# batt.net
KiCad netlist of a schematic drawn in Altium Designer
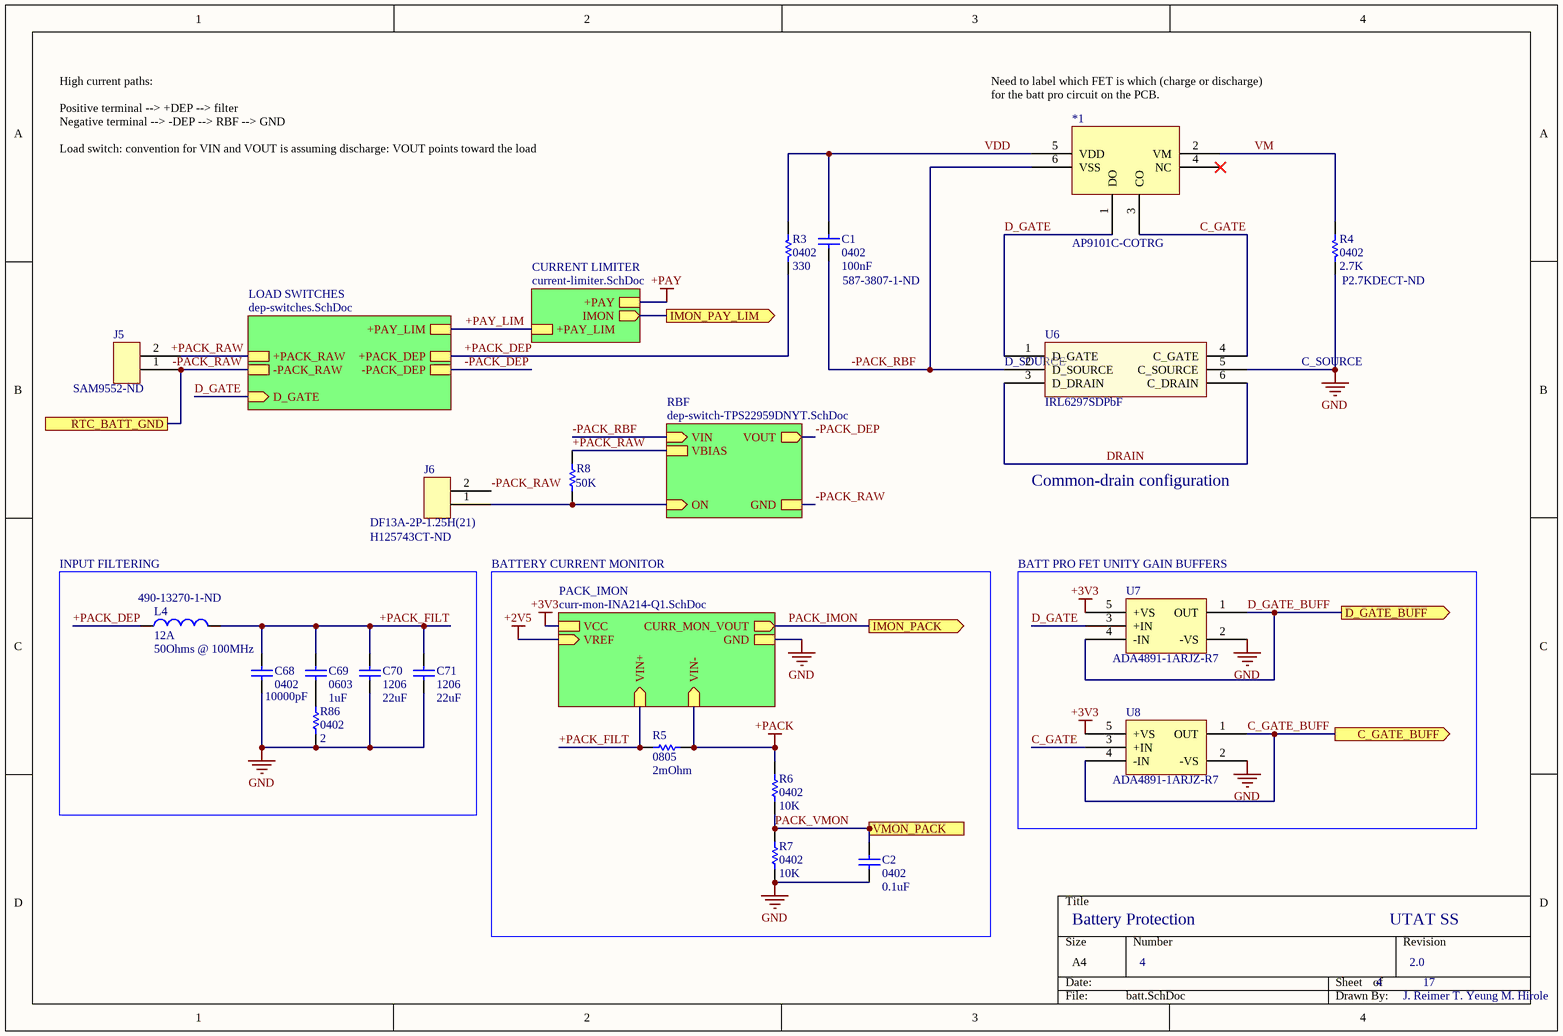
[diagram p0: batt.SchDoc]

(export (version "E")
  (design (tool "Eeschema 10.0.6"))
  (components
    (comp (ref "*1")
      (value "AP9101C-COTRG")
      (footprint "SOT-26")
      (description "Battery Protection IC")
      (libsource (lib "heron-general") (part "AP9101C-COTRG"))
    )
    (comp (ref "C1")
      (value "0402")
      (footprint "CAP0402R")
      (description "0402 capacitor")
      (fields
        (field (name "ALTIUM_VALUE") "100nF")
        (field (name "SUPPLIER PART NUMBER 1") "587-3807-1-ND")
        (field (name "MANUFACTURER") "Taiyo Yuden")
        (field (name "MANUFACTURER PART NUMBER") "EMK105B7104KVHF")
      )
      (libsource (lib "heron-general") (part "CAP0402"))
    )
    (comp (ref "C2")
      (value "0402")
      (footprint "CAP0402R")
      (description "0402 capacitor")
      (fields (field (name "ALTIUM_VALUE") "0.1uF"))
      (libsource (lib "heron-general") (part "CAP0402"))
    )
    (comp (ref "C68")
      (value "0402")
      (footprint "CAP0402R")
      (description "Capacitor")
      (fields (field (name "ALTIUM_VALUE") "10000pF") (field (name "PUBLISHER") "Altium Limited"))
      (libsource (lib "Miscellaneous Devices") (part "Cap"))
    )
    (comp (ref "C69")
      (value "0603")
      (footprint "CAP0603R")
      (description "Capacitor")
      (fields (field (name "ALTIUM_VALUE") "1uF") (field (name "PUBLISHER") "Altium Limited"))
      (libsource (lib "Miscellaneous Devices") (part "Cap"))
    )
    (comp (ref "C70")
      (value "1206")
      (footprint "CAP1206R")
      (description "1206 capacitor")
      (fields (field (name "ALTIUM_VALUE") "22uF"))
      (libsource (lib "heron-general") (part "CAP1206"))
    )
    (comp (ref "C71")
      (value "1206")
      (footprint "CAP1206R")
      (description "1206 capacitor")
      (fields (field (name "ALTIUM_VALUE") "22uF"))
      (libsource (lib "heron-general") (part "CAP1206"))
    )
    (comp (ref "J5")
      (value "IPBT-102-H1-T-S-RA-K")
      (footprint "SAM9552-ND")
      (description "Samtec Connector Through Hole, Right Angle 2 pos 0.165\" (4.20mm) pitch")
      (fields (field (name "SUPPLIER PART NUMBER 1") "SAM9552-ND"))
      (libsource (lib "heron-general") (part "IPBT-102-H1-T-S-RA-K"))
    )
    (comp (ref "J6")
      (value "DF13A-2P-1.25H(21)")
      (footprint "DF13A-2P-1.25H(21)")
      (description "2 pos DF13 right angle surface mount connector")
      (fields (field (name "SUPPLIER PART NUMBER 1") "H125743CT-ND"))
      (libsource (lib "heron-general") (part "DF13A-2P-1.25H(21)"))
    )
    (comp (ref "L4")
      (value "12A")
      (footprint "CAP1206R")
      (description "Inductor 50Ohms @ 100MHz")
      (fields
        (field (name "ALTIUM_VALUE") "50Ohms @ 100MHz")
        (field (name "SUPPLIER PART NUMBER 3") "490-13270-1-ND")
        (field (name "PUBLISHER") "Altium Limited")
      )
      (libsource (lib "Miscellaneous Devices") (part "Inductor"))
    )
    (comp (ref "R3")
      (value "0402")
      (footprint "RES0402R")
      (description "0402 resistor")
      (fields (field (name "ALTIUM_VALUE") "330"))
      (libsource (lib "heron-general") (part "RES0402"))
    )
    (comp (ref "R4")
      (value "0402")
      (footprint "RES0402R")
      (description "0402 resistor")
      (fields
        (field (name "ALTIUM_VALUE") "2.7K")
        (field (name "SUPPLIER PART NUMBER 1") "P2.7KDECT-ND")
        (field (name "MANUFACTURER") "Panasonic")
        (field (name "MANUFACTURER PART NUMBER") "ERA-2AED272X")
      )
      (libsource (lib "heron-general") (part "RES0402"))
    )
    (comp (ref "R5")
      (value "0805")
      (footprint "RES0805R")
      (description "0805 resistor")
      (fields
        (field (name "ALTIUM_VALUE") "2mOhm")
        (field (name "MANUFACTURER") "Panasonic")
        (field (name "MANUFACTURER PART NUMBER") "ERJ-8BWJR010V")
      )
      (libsource (lib "heron-general") (part "RES0805"))
    )
    (comp (ref "R6")
      (value "0402")
      (footprint "RES0402R")
      (description "0402 resistor")
      (fields (field (name "ALTIUM_VALUE") "10K"))
      (libsource (lib "heron-general") (part "RES0402"))
    )
    (comp (ref "R7")
      (value "0402")
      (footprint "RES0402R")
      (description "0402 resistor")
      (fields (field (name "ALTIUM_VALUE") "10K"))
      (libsource (lib "heron-general") (part "RES0402"))
    )
    (comp (ref "R8")
      (value "50K")
      (footprint "RES0402R")
      (description "0402 resistor")
      (fields (field (name "Comment") "0402"))
      (libsource (lib "heron-general") (part "RES0402"))
    )
    (comp (ref "R86")
      (value "0402")
      (footprint "RES0402R")
      (description "Resistor")
      (fields (field (name "ALTIUM_VALUE") "2") (field (name "PUBLISHER") "Altium Limited"))
      (libsource (lib "Miscellaneous Devices") (part "Res1"))
    )
    (comp (ref "U6")
      (value "IRL6297SDPbF")
      (footprint "IRL6297SDPbF")
      (libsource (lib "heron-general") (part "IRL6297SDPbF"))
    )
    (comp (ref "U7")
      (value "ADA4891-1ARJZ-R7")
      (footprint "SOT-23-5")
      (description "Rail-to-rail amplifier 125mA max")
      (fields (field (name "COPYRIGHT") "Copyright (C) 2018 Accelerated Designs. All rights reserved"))
      (libsource (lib "heron-general") (part "ADA4891-1ARJZ-R7"))
    )
    (comp (ref "U8")
      (value "ADA4891-1ARJZ-R7")
      (footprint "SOT-23-5")
      (description "Rail-to-rail amplifier 125mA max")
      (fields (field (name "COPYRIGHT") "Copyright (C) 2018 Accelerated Designs. All rights reserved"))
      (libsource (lib "heron-general") (part "ADA4891-1ARJZ-R7"))
    )
  )
  (nets
    (net (code "2") (name "+3V3") (class "Default")
      (node (ref "U7") (pin "5") (pinfunction "+VS_5") (pintype "passive"))
      (node (ref "U8") (pin "5") (pinfunction "+VS_5") (pintype "passive"))
    )
    (net (code "3") (name "+PACK") (class "Default")
      (node (ref "R5") (pin "2") (pinfunction "2_2") (pintype "passive"))
      (node (ref "R6") (pin "2") (pinfunction "2_2") (pintype "passive"))
    )
    (net (code "5") (name "/+PACK_DEP") (class "Default")
      (node (ref "L4") (pin "1") (pinfunction "1_1") (pintype "passive"))
      (node (ref "R3") (pin "2") (pinfunction "2_2") (pintype "passive"))
    )
    (net (code "6") (name "/+PACK_FILT") (class "Default")
      (node (ref "C68") (pin "2") (pinfunction "2_2") (pintype "passive"))
      (node (ref "C69") (pin "2") (pinfunction "2_2") (pintype "passive"))
      (node (ref "C70") (pin "2") (pinfunction "2_2") (pintype "passive"))
      (node (ref "C71") (pin "2") (pinfunction "2_2") (pintype "passive"))
      (node (ref "L4") (pin "2") (pinfunction "2_2") (pintype "passive"))
      (node (ref "R5") (pin "1") (pinfunction "1_1") (pintype "passive"))
    )
    (net (code "7") (name "/+PACK_RAW") (class "Default")
      (node (ref "J5") (pin "2") (pinfunction "2_2") (pintype "passive"))
      (node (ref "R8") (pin "2") (pinfunction "2_2") (pintype "passive"))
    )
    (net (code "10") (name "/-PACK_RAW") (class "Default")
      (node (ref "J5") (pin "1") (pinfunction "1_1") (pintype "passive"))
      (node (ref "J6") (pin "2") (pintype "passive"))
    )
    (net (code "11") (name "/-PACK_RBF") (class "Default")
      (node (ref "*1") (pin "6") (pinfunction "VSS_6") (pintype "passive"))
      (node (ref "C1") (pin "1") (pinfunction "1_1") (pintype "passive"))
      (node (ref "U6") (pin "2") (pinfunction "D_SOURCE_2") (pintype "passive"))
    )
    (net (code "13") (name "/C_GATE") (class "Default")
      (node (ref "*1") (pin "3") (pinfunction "CO_3") (pintype "passive"))
      (node (ref "U6") (pin "4") (pinfunction "C_GATE_4") (pintype "passive"))
      (node (ref "U8") (pin "3") (pinfunction "+IN_3") (pintype "passive"))
    )
    (net (code "14") (name "/C_GATE_BUFF") (class "Default")
      (node (ref "U8") (pin "1") (pinfunction "OUT_1") (pintype "passive"))
      (node (ref "U8") (pin "4") (pinfunction "-IN_4") (pintype "passive"))
    )
    (net (code "15") (name "/DRAIN") (class "Default")
      (node (ref "U6") (pin "3") (pinfunction "D_DRAIN_3") (pintype "passive"))
      (node (ref "U6") (pin "6") (pinfunction "C_DRAIN_6") (pintype "passive"))
    )
    (net (code "16") (name "/D_GATE") (class "Default")
      (node (ref "*1") (pin "1") (pinfunction "DO_1") (pintype "passive"))
      (node (ref "U6") (pin "1") (pinfunction "D_GATE_1") (pintype "passive"))
      (node (ref "U7") (pin "3") (pinfunction "+IN_3") (pintype "passive"))
    )
    (net (code "17") (name "/D_GATE_BUFF") (class "Default")
      (node (ref "U7") (pin "1") (pinfunction "OUT_1") (pintype "passive"))
      (node (ref "U7") (pin "4") (pinfunction "-IN_4") (pintype "passive"))
    )
    (net (code "19") (name "/ON") (class "Default")
      (node (ref "J6") (pin "1") (pintype "passive"))
      (node (ref "R8") (pin "1") (pinfunction "1_1") (pintype "passive"))
    )
    (net (code "21") (name "/PACK_VMON") (class "Default")
      (node (ref "C2") (pin "2") (pinfunction "2_2") (pintype "passive"))
      (node (ref "R6") (pin "1") (pinfunction "1_1") (pintype "passive"))
      (node (ref "R7") (pin "2") (pinfunction "2_2") (pintype "passive"))
    )
    (net (code "22") (name "/VDD") (class "Default")
      (node (ref "*1") (pin "5") (pinfunction "VDD_5") (pintype "passive"))
      (node (ref "C1") (pin "2") (pinfunction "2_2") (pintype "passive"))
      (node (ref "R3") (pin "1") (pinfunction "1_1") (pintype "passive"))
    )
    (net (code "23") (name "/VM") (class "Default")
      (node (ref "*1") (pin "2") (pinfunction "VM_2") (pintype "passive"))
      (node (ref "R4") (pin "2") (pinfunction "2_2") (pintype "passive"))
    )
    (net (code "24") (name "GND") (class "Default")
      (node (ref "C2") (pin "1") (pinfunction "1_1") (pintype "passive"))
      (node (ref "C68") (pin "1") (pinfunction "1_1") (pintype "passive"))
      (node (ref "C70") (pin "1") (pinfunction "1_1") (pintype "passive"))
      (node (ref "C71") (pin "1") (pinfunction "1_1") (pintype "passive"))
      (node (ref "R4") (pin "1") (pinfunction "1_1") (pintype "passive"))
      (node (ref "R7") (pin "1") (pinfunction "1_1") (pintype "passive"))
      (node (ref "R86") (pin "1") (pinfunction "1_1") (pintype "passive"))
      (node (ref "U6") (pin "5") (pinfunction "C_SOURCE_5") (pintype "passive"))
      (node (ref "U7") (pin "2") (pinfunction "-VS_2") (pintype "passive"))
      (node (ref "U8") (pin "2") (pinfunction "-VS_2") (pintype "passive"))
    )
    (net (code "25") (name "Net-(C69-Pad1)") (class "Default")
      (node (ref "C69") (pin "1") (pinfunction "1_1") (pintype "passive"))
      (node (ref "R86") (pin "2") (pinfunction "2_2") (pintype "passive"))
    )
    (net (code "26") (name "unconnected-(*1-NC-Pad4)") (class "Default")
      (node (ref "*1") (pin "4") (pinfunction "NC_4") (pintype "passive+no_connect"))
    )
  )
)
